# relay-set-d-decode.net
KiCad netlist of a schematic drawn in EAGLE
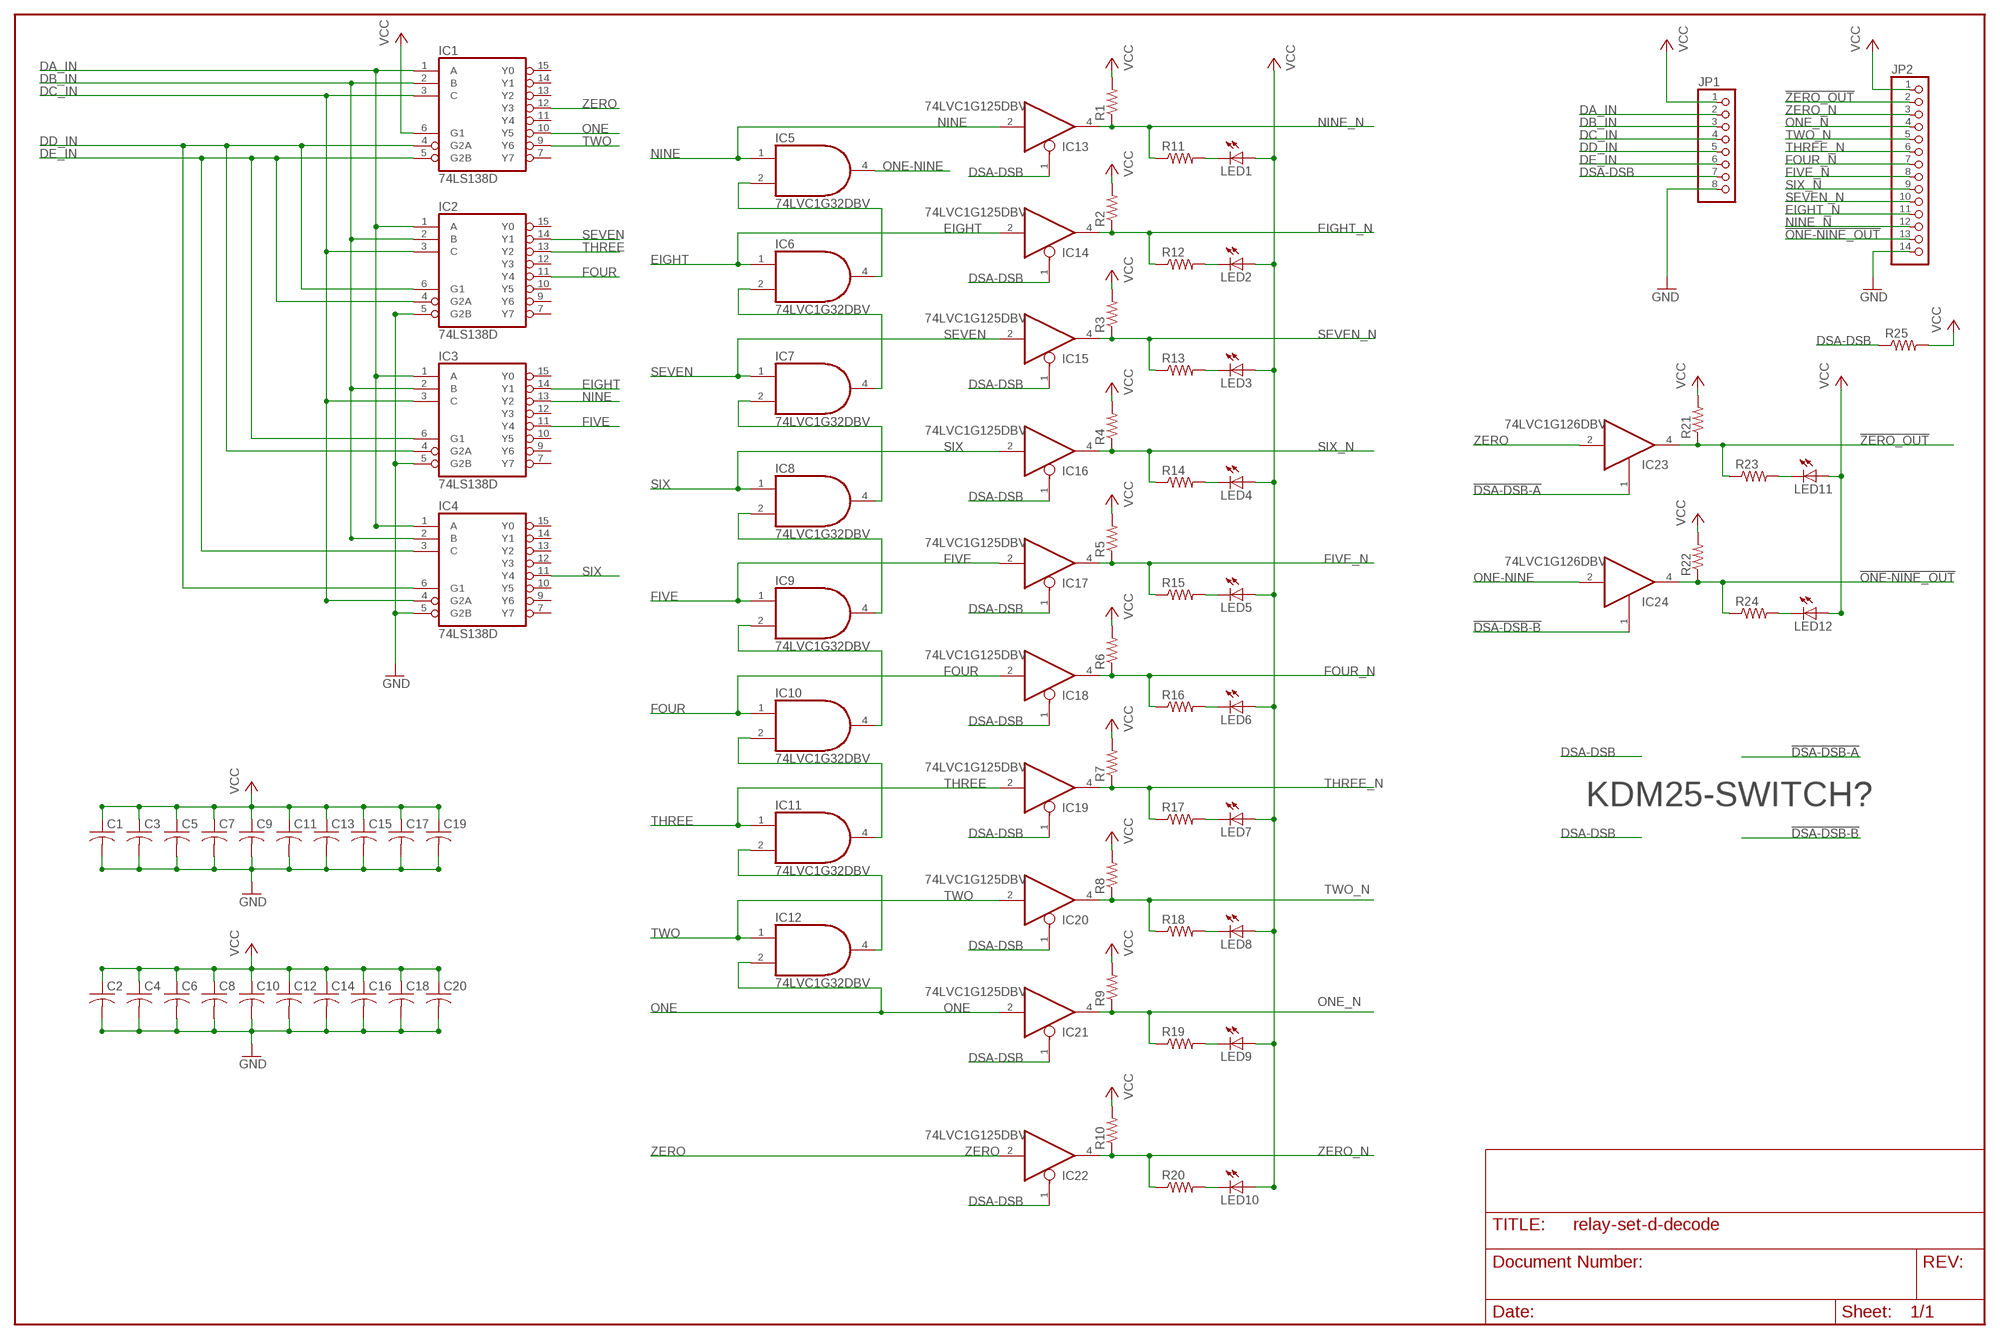
[diagram p0: schematic, sheet 1]

(export (version "E")
  (design (tool "Eeschema 10.0.6"))
  (components
    (comp (ref "C1")
      (value "C-USC0805")
      (footprint "eagle-import:C0805")
      (libsource (lib "eagle-import") (part "C-USC0805"))
    )
    (comp (ref "C2")
      (value "C-USC0805")
      (footprint "eagle-import:C0805")
      (libsource (lib "eagle-import") (part "C-USC0805"))
    )
    (comp (ref "C3")
      (value "C-USC0805")
      (footprint "eagle-import:C0805")
      (libsource (lib "eagle-import") (part "C-USC0805"))
    )
    (comp (ref "C4")
      (value "C-USC0805")
      (footprint "eagle-import:C0805")
      (libsource (lib "eagle-import") (part "C-USC0805"))
    )
    (comp (ref "C5")
      (value "C-USC0805")
      (footprint "eagle-import:C0805")
      (libsource (lib "eagle-import") (part "C-USC0805"))
    )
    (comp (ref "C6")
      (value "C-USC0805")
      (footprint "eagle-import:C0805")
      (libsource (lib "eagle-import") (part "C-USC0805"))
    )
    (comp (ref "C7")
      (value "C-USC0805")
      (footprint "eagle-import:C0805")
      (libsource (lib "eagle-import") (part "C-USC0805"))
    )
    (comp (ref "C8")
      (value "C-USC0805")
      (footprint "eagle-import:C0805")
      (libsource (lib "eagle-import") (part "C-USC0805"))
    )
    (comp (ref "C9")
      (value "C-USC0805")
      (footprint "eagle-import:C0805")
      (libsource (lib "eagle-import") (part "C-USC0805"))
    )
    (comp (ref "C10")
      (value "C-USC0805")
      (footprint "eagle-import:C0805")
      (libsource (lib "eagle-import") (part "C-USC0805"))
    )
    (comp (ref "C11")
      (value "C-USC0805")
      (footprint "eagle-import:C0805")
      (libsource (lib "eagle-import") (part "C-USC0805"))
    )
    (comp (ref "C12")
      (value "C-USC0805")
      (footprint "eagle-import:C0805")
      (libsource (lib "eagle-import") (part "C-USC0805"))
    )
    (comp (ref "C13")
      (value "C-USC0805")
      (footprint "eagle-import:C0805")
      (libsource (lib "eagle-import") (part "C-USC0805"))
    )
    (comp (ref "C14")
      (value "C-USC0805")
      (footprint "eagle-import:C0805")
      (libsource (lib "eagle-import") (part "C-USC0805"))
    )
    (comp (ref "C15")
      (value "C-USC0805")
      (footprint "eagle-import:C0805")
      (libsource (lib "eagle-import") (part "C-USC0805"))
    )
    (comp (ref "C16")
      (value "C-USC0805")
      (footprint "eagle-import:C0805")
      (libsource (lib "eagle-import") (part "C-USC0805"))
    )
    (comp (ref "C17")
      (value "C-USC0805")
      (footprint "eagle-import:C0805")
      (libsource (lib "eagle-import") (part "C-USC0805"))
    )
    (comp (ref "C18")
      (value "C-USC0805")
      (footprint "eagle-import:C0805")
      (libsource (lib "eagle-import") (part "C-USC0805"))
    )
    (comp (ref "C19")
      (value "C-USC0805")
      (footprint "eagle-import:C0805")
      (libsource (lib "eagle-import") (part "C-USC0805"))
    )
    (comp (ref "C20")
      (value "C-USC0805")
      (footprint "eagle-import:C0805")
      (libsource (lib "eagle-import") (part "C-USC0805"))
    )
    (comp (ref "IC1")
      (value "74LS138D")
      (footprint "eagle-import:SO16")
      (libsource (lib "eagle-import") (part "74138DLS"))
    )
    (comp (ref "IC2")
      (value "74LS138D")
      (footprint "eagle-import:SO16")
      (libsource (lib "eagle-import") (part "74138DLS"))
    )
    (comp (ref "IC3")
      (value "74LS138D")
      (footprint "eagle-import:SO16")
      (libsource (lib "eagle-import") (part "74138DLS"))
    )
    (comp (ref "IC4")
      (value "74LS138D")
      (footprint "eagle-import:SO16")
      (libsource (lib "eagle-import") (part "74138DLS"))
    )
    (comp (ref "IC5")
      (value "74LVC1G32DBV")
      (footprint "eagle-import:SOT23-5")
      (libsource (lib "eagle-import") (part "741G08DBVLVC"))
    )
    (comp (ref "IC6")
      (value "74LVC1G32DBV")
      (footprint "eagle-import:SOT23-5")
      (libsource (lib "eagle-import") (part "741G08DBVLVC"))
    )
    (comp (ref "IC7")
      (value "74LVC1G32DBV")
      (footprint "eagle-import:SOT23-5")
      (libsource (lib "eagle-import") (part "741G08DBVLVC"))
    )
    (comp (ref "IC8")
      (value "74LVC1G32DBV")
      (footprint "eagle-import:SOT23-5")
      (libsource (lib "eagle-import") (part "741G08DBVLVC"))
    )
    (comp (ref "IC9")
      (value "74LVC1G32DBV")
      (footprint "eagle-import:SOT23-5")
      (libsource (lib "eagle-import") (part "741G08DBVLVC"))
    )
    (comp (ref "IC10")
      (value "74LVC1G32DBV")
      (footprint "eagle-import:SOT23-5")
      (libsource (lib "eagle-import") (part "741G08DBVLVC"))
    )
    (comp (ref "IC11")
      (value "74LVC1G32DBV")
      (footprint "eagle-import:SOT23-5")
      (libsource (lib "eagle-import") (part "741G08DBVLVC"))
    )
    (comp (ref "IC12")
      (value "74LVC1G32DBV")
      (footprint "eagle-import:SOT23-5")
      (libsource (lib "eagle-import") (part "741G08DBVLVC"))
    )
    (comp (ref "IC13")
      (value "74LVC1G125DBV")
      (footprint "eagle-import:SOT23-5")
      (libsource (lib "eagle-import") (part "741G125DBVLVC"))
    )
    (comp (ref "IC14")
      (value "74LVC1G125DBV")
      (footprint "eagle-import:SOT23-5")
      (libsource (lib "eagle-import") (part "741G125DBVLVC"))
    )
    (comp (ref "IC15")
      (value "74LVC1G125DBV")
      (footprint "eagle-import:SOT23-5")
      (libsource (lib "eagle-import") (part "741G125DBVLVC"))
    )
    (comp (ref "IC16")
      (value "74LVC1G125DBV")
      (footprint "eagle-import:SOT23-5")
      (libsource (lib "eagle-import") (part "741G125DBVLVC"))
    )
    (comp (ref "IC17")
      (value "74LVC1G125DBV")
      (footprint "eagle-import:SOT23-5")
      (libsource (lib "eagle-import") (part "741G125DBVLVC"))
    )
    (comp (ref "IC18")
      (value "74LVC1G125DBV")
      (footprint "eagle-import:SOT23-5")
      (libsource (lib "eagle-import") (part "741G125DBVLVC"))
    )
    (comp (ref "IC19")
      (value "74LVC1G125DBV")
      (footprint "eagle-import:SOT23-5")
      (libsource (lib "eagle-import") (part "741G125DBVLVC"))
    )
    (comp (ref "IC20")
      (value "74LVC1G125DBV")
      (footprint "eagle-import:SOT23-5")
      (libsource (lib "eagle-import") (part "741G125DBVLVC"))
    )
    (comp (ref "IC21")
      (value "74LVC1G125DBV")
      (footprint "eagle-import:SOT23-5")
      (libsource (lib "eagle-import") (part "741G125DBVLVC"))
    )
    (comp (ref "IC22")
      (value "74LVC1G125DBV")
      (footprint "eagle-import:SOT23-5")
      (libsource (lib "eagle-import") (part "741G125DBVLVC"))
    )
    (comp (ref "IC23")
      (value "74LVC1G126DBV")
      (footprint "eagle-import:SOT23-5")
      (libsource (lib "eagle-import") (part "741G126DBVLVC"))
    )
    (comp (ref "IC24")
      (value "74LVC1G126DBV")
      (footprint "eagle-import:SOT23-5")
      (libsource (lib "eagle-import") (part "741G126DBVLVC"))
    )
    (comp (ref "JP1")
      (value "PINHD-1X8")
      (footprint "eagle-import:1X08")
      (libsource (lib "eagle-import") (part "PINHD-1X8"))
    )
    (comp (ref "JP2")
      (value "PINHD-1X14")
      (footprint "eagle-import:1X14")
      (libsource (lib "eagle-import") (part "PINHD-1X14"))
    )
    (comp (ref "LED1")
      (value "LEDCHIP-LED0805")
      (footprint "eagle-import:CHIP-LED0805")
      (libsource (lib "eagle-import") (part "LEDCHIP-LED0805"))
    )
    (comp (ref "LED2")
      (value "LEDCHIP-LED0805")
      (footprint "eagle-import:CHIP-LED0805")
      (libsource (lib "eagle-import") (part "LEDCHIP-LED0805"))
    )
    (comp (ref "LED3")
      (value "LEDCHIP-LED0805")
      (footprint "eagle-import:CHIP-LED0805")
      (libsource (lib "eagle-import") (part "LEDCHIP-LED0805"))
    )
    (comp (ref "LED4")
      (value "LEDCHIP-LED0805")
      (footprint "eagle-import:CHIP-LED0805")
      (libsource (lib "eagle-import") (part "LEDCHIP-LED0805"))
    )
    (comp (ref "LED5")
      (value "LEDCHIP-LED0805")
      (footprint "eagle-import:CHIP-LED0805")
      (libsource (lib "eagle-import") (part "LEDCHIP-LED0805"))
    )
    (comp (ref "LED6")
      (value "LEDCHIP-LED0805")
      (footprint "eagle-import:CHIP-LED0805")
      (libsource (lib "eagle-import") (part "LEDCHIP-LED0805"))
    )
    (comp (ref "LED7")
      (value "LEDCHIP-LED0805")
      (footprint "eagle-import:CHIP-LED0805")
      (libsource (lib "eagle-import") (part "LEDCHIP-LED0805"))
    )
    (comp (ref "LED8")
      (value "LEDCHIP-LED0805")
      (footprint "eagle-import:CHIP-LED0805")
      (libsource (lib "eagle-import") (part "LEDCHIP-LED0805"))
    )
    (comp (ref "LED9")
      (value "LEDCHIP-LED0805")
      (footprint "eagle-import:CHIP-LED0805")
      (libsource (lib "eagle-import") (part "LEDCHIP-LED0805"))
    )
    (comp (ref "LED10")
      (value "LEDCHIP-LED0805")
      (footprint "eagle-import:CHIP-LED0805")
      (libsource (lib "eagle-import") (part "LEDCHIP-LED0805"))
    )
    (comp (ref "LED11")
      (value "LEDCHIP-LED0805")
      (footprint "eagle-import:CHIP-LED0805")
      (libsource (lib "eagle-import") (part "LEDCHIP-LED0805"))
    )
    (comp (ref "LED12")
      (value "LEDCHIP-LED0805")
      (footprint "eagle-import:CHIP-LED0805")
      (libsource (lib "eagle-import") (part "LEDCHIP-LED0805"))
    )
    (comp (ref "R1")
      (value "R-US_R0805")
      (footprint "eagle-import:R0805")
      (libsource (lib "eagle-import") (part "R-US_R0805"))
    )
    (comp (ref "R2")
      (value "R-US_R0805")
      (footprint "eagle-import:R0805")
      (libsource (lib "eagle-import") (part "R-US_R0805"))
    )
    (comp (ref "R3")
      (value "R-US_R0805")
      (footprint "eagle-import:R0805")
      (libsource (lib "eagle-import") (part "R-US_R0805"))
    )
    (comp (ref "R4")
      (value "R-US_R0805")
      (footprint "eagle-import:R0805")
      (libsource (lib "eagle-import") (part "R-US_R0805"))
    )
    (comp (ref "R5")
      (value "R-US_R0805")
      (footprint "eagle-import:R0805")
      (libsource (lib "eagle-import") (part "R-US_R0805"))
    )
    (comp (ref "R6")
      (value "R-US_R0805")
      (footprint "eagle-import:R0805")
      (libsource (lib "eagle-import") (part "R-US_R0805"))
    )
    (comp (ref "R7")
      (value "R-US_R0805")
      (footprint "eagle-import:R0805")
      (libsource (lib "eagle-import") (part "R-US_R0805"))
    )
    (comp (ref "R8")
      (value "R-US_R0805")
      (footprint "eagle-import:R0805")
      (libsource (lib "eagle-import") (part "R-US_R0805"))
    )
    (comp (ref "R9")
      (value "R-US_R0805")
      (footprint "eagle-import:R0805")
      (libsource (lib "eagle-import") (part "R-US_R0805"))
    )
    (comp (ref "R10")
      (value "R-US_R0805")
      (footprint "eagle-import:R0805")
      (libsource (lib "eagle-import") (part "R-US_R0805"))
    )
    (comp (ref "R11")
      (value "R-US_R0805")
      (footprint "eagle-import:R0805")
      (libsource (lib "eagle-import") (part "R-US_R0805"))
    )
    (comp (ref "R12")
      (value "R-US_R0805")
      (footprint "eagle-import:R0805")
      (libsource (lib "eagle-import") (part "R-US_R0805"))
    )
    (comp (ref "R13")
      (value "R-US_R0805")
      (footprint "eagle-import:R0805")
      (libsource (lib "eagle-import") (part "R-US_R0805"))
    )
    (comp (ref "R14")
      (value "R-US_R0805")
      (footprint "eagle-import:R0805")
      (libsource (lib "eagle-import") (part "R-US_R0805"))
    )
    (comp (ref "R15")
      (value "R-US_R0805")
      (footprint "eagle-import:R0805")
      (libsource (lib "eagle-import") (part "R-US_R0805"))
    )
    (comp (ref "R16")
      (value "R-US_R0805")
      (footprint "eagle-import:R0805")
      (libsource (lib "eagle-import") (part "R-US_R0805"))
    )
    (comp (ref "R17")
      (value "R-US_R0805")
      (footprint "eagle-import:R0805")
      (libsource (lib "eagle-import") (part "R-US_R0805"))
    )
    (comp (ref "R18")
      (value "R-US_R0805")
      (footprint "eagle-import:R0805")
      (libsource (lib "eagle-import") (part "R-US_R0805"))
    )
    (comp (ref "R19")
      (value "R-US_R0805")
      (footprint "eagle-import:R0805")
      (libsource (lib "eagle-import") (part "R-US_R0805"))
    )
    (comp (ref "R20")
      (value "R-US_R0805")
      (footprint "eagle-import:R0805")
      (libsource (lib "eagle-import") (part "R-US_R0805"))
    )
    (comp (ref "R21")
      (value "R-US_R0805")
      (footprint "eagle-import:R0805")
      (libsource (lib "eagle-import") (part "R-US_R0805"))
    )
    (comp (ref "R22")
      (value "R-US_R0805")
      (footprint "eagle-import:R0805")
      (libsource (lib "eagle-import") (part "R-US_R0805"))
    )
    (comp (ref "R23")
      (value "R-US_R0805")
      (footprint "eagle-import:R0805")
      (libsource (lib "eagle-import") (part "R-US_R0805"))
    )
    (comp (ref "R24")
      (value "R-US_R0805")
      (footprint "eagle-import:R0805")
      (libsource (lib "eagle-import") (part "R-US_R0805"))
    )
    (comp (ref "R25")
      (value "R-US_R0805")
      (footprint "eagle-import:R0805")
      (libsource (lib "eagle-import") (part "R-US_R0805"))
    )
  )
  (nets
    (net (code "1") (name "/DA_IN") (class "Default")
      (node (ref "IC1") (pin "1") (pinfunction "A_1") (pintype "input"))
      (node (ref "IC2") (pin "1") (pinfunction "A_1") (pintype "input"))
      (node (ref "IC3") (pin "1") (pinfunction "A_1") (pintype "input"))
      (node (ref "IC4") (pin "1") (pinfunction "A_1") (pintype "input"))
      (node (ref "JP1") (pin "2") (pinfunction "2_2") (pintype "passive"))
    )
    (net (code "2") (name "/DB_IN") (class "Default")
      (node (ref "IC1") (pin "2") (pinfunction "B_2") (pintype "input"))
      (node (ref "IC2") (pin "2") (pinfunction "B_2") (pintype "input"))
      (node (ref "IC3") (pin "2") (pinfunction "B_2") (pintype "input"))
      (node (ref "IC4") (pin "2") (pinfunction "B_2") (pintype "input"))
      (node (ref "JP1") (pin "3") (pinfunction "3_3") (pintype "passive"))
    )
    (net (code "3") (name "/DC_IN") (class "Default")
      (node (ref "IC1") (pin "3") (pinfunction "C_3") (pintype "input"))
      (node (ref "IC2") (pin "3") (pinfunction "C_3") (pintype "input"))
      (node (ref "IC3") (pin "3") (pinfunction "C_3") (pintype "input"))
      (node (ref "IC4") (pin "4") (pinfunction "G2A_4") (pintype "input"))
      (node (ref "JP1") (pin "4") (pinfunction "4_4") (pintype "passive"))
    )
    (net (code "4") (name "/DD_IN") (class "Default")
      (node (ref "IC1") (pin "4") (pinfunction "G2A_4") (pintype "input"))
      (node (ref "IC2") (pin "6") (pinfunction "G1_6") (pintype "input"))
      (node (ref "IC3") (pin "4") (pinfunction "G2A_4") (pintype "input"))
      (node (ref "IC4") (pin "6") (pinfunction "G1_6") (pintype "input"))
      (node (ref "JP1") (pin "5") (pinfunction "5_5") (pintype "passive"))
    )
    (net (code "5") (name "/DE_IN") (class "Default")
      (node (ref "IC1") (pin "5") (pinfunction "G2B_5") (pintype "input"))
      (node (ref "IC2") (pin "4") (pinfunction "G2A_4") (pintype "input"))
      (node (ref "IC3") (pin "6") (pinfunction "G1_6") (pintype "input"))
      (node (ref "IC4") (pin "3") (pinfunction "C_3") (pintype "input"))
      (node (ref "JP1") (pin "6") (pinfunction "6_6") (pintype "passive"))
    )
    (net (code "6") (name "/DSA-DSB") (class "Default")
      (node (ref "IC13") (pin "1") (pinfunction "OE_1") (pintype "input"))
      (node (ref "IC14") (pin "1") (pinfunction "OE_1") (pintype "input"))
      (node (ref "IC15") (pin "1") (pinfunction "OE_1") (pintype "input"))
      (node (ref "IC16") (pin "1") (pinfunction "OE_1") (pintype "input"))
      (node (ref "IC17") (pin "1") (pinfunction "OE_1") (pintype "input"))
      (node (ref "IC18") (pin "1") (pinfunction "OE_1") (pintype "input"))
      (node (ref "IC19") (pin "1") (pinfunction "OE_1") (pintype "input"))
      (node (ref "IC20") (pin "1") (pinfunction "OE_1") (pintype "input"))
      (node (ref "IC21") (pin "1") (pinfunction "OE_1") (pintype "input"))
      (node (ref "IC22") (pin "1") (pinfunction "OE_1") (pintype "input"))
      (node (ref "JP1") (pin "7") (pinfunction "7_7") (pintype "passive"))
      (node (ref "R25") (pin "1") (pinfunction "1_1") (pintype "passive"))
    )
    (net (code "7") (name "/EIGHT") (class "Default")
      (node (ref "IC14") (pin "2") (pinfunction "I_2") (pintype "input"))
      (node (ref "IC3") (pin "14") (pinfunction "Y1_14") (pintype "output"))
      (node (ref "IC6") (pin "1") (pinfunction "I0_1") (pintype "input"))
    )
    (net (code "8") (name "/EIGHT_N") (class "Default")
      (node (ref "IC14") (pin "4") (pinfunction "O_4") (pintype "tri_state"))
      (node (ref "JP2") (pin "11") (pinfunction "11_11") (pintype "passive"))
      (node (ref "R12") (pin "1") (pinfunction "1_1") (pintype "passive"))
      (node (ref "R2") (pin "1") (pinfunction "1_1") (pintype "passive"))
    )
    (net (code "9") (name "/FIVE") (class "Default")
      (node (ref "IC17") (pin "2") (pinfunction "I_2") (pintype "input"))
      (node (ref "IC3") (pin "11") (pinfunction "Y4_11") (pintype "output"))
      (node (ref "IC9") (pin "1") (pinfunction "I0_1") (pintype "input"))
    )
    (net (code "10") (name "/FIVE_N") (class "Default")
      (node (ref "IC17") (pin "4") (pinfunction "O_4") (pintype "tri_state"))
      (node (ref "JP2") (pin "8") (pinfunction "8_8") (pintype "passive"))
      (node (ref "R15") (pin "1") (pinfunction "1_1") (pintype "passive"))
      (node (ref "R5") (pin "1") (pinfunction "1_1") (pintype "passive"))
    )
    (net (code "11") (name "/FOUR") (class "Default")
      (node (ref "IC10") (pin "1") (pinfunction "I0_1") (pintype "input"))
      (node (ref "IC18") (pin "2") (pinfunction "I_2") (pintype "input"))
      (node (ref "IC2") (pin "11") (pinfunction "Y4_11") (pintype "output"))
    )
    (net (code "12") (name "/FOUR_N") (class "Default")
      (node (ref "IC18") (pin "4") (pinfunction "O_4") (pintype "tri_state"))
      (node (ref "JP2") (pin "7") (pinfunction "7_7") (pintype "passive"))
      (node (ref "R16") (pin "1") (pinfunction "1_1") (pintype "passive"))
      (node (ref "R6") (pin "1") (pinfunction "1_1") (pintype "passive"))
    )
    (net (code "13") (name "/NINE") (class "Default")
      (node (ref "IC13") (pin "2") (pinfunction "I_2") (pintype "input"))
      (node (ref "IC3") (pin "13") (pinfunction "Y2_13") (pintype "output"))
      (node (ref "IC5") (pin "1") (pinfunction "I0_1") (pintype "input"))
    )
    (net (code "14") (name "/NINE_N") (class "Default")
      (node (ref "IC13") (pin "4") (pinfunction "O_4") (pintype "tri_state"))
      (node (ref "JP2") (pin "12") (pinfunction "12_12") (pintype "passive"))
      (node (ref "R1") (pin "1") (pinfunction "1_1") (pintype "passive"))
      (node (ref "R11") (pin "1") (pinfunction "1_1") (pintype "passive"))
    )
    (net (code "15") (name "/ONE") (class "Default")
      (node (ref "IC1") (pin "10") (pinfunction "Y5_10") (pintype "output"))
      (node (ref "IC12") (pin "2") (pinfunction "I1_2") (pintype "input"))
      (node (ref "IC21") (pin "2") (pinfunction "I_2") (pintype "input"))
    )
    (net (code "16") (name "/ONE-NINE") (class "Default")
      (node (ref "IC24") (pin "2") (pinfunction "I_2") (pintype "input"))
      (node (ref "IC5") (pin "4") (pinfunction "O_4") (pintype "output"))
    )
    (net (code "17") (name "/ONE_N") (class "Default")
      (node (ref "IC21") (pin "4") (pinfunction "O_4") (pintype "tri_state"))
      (node (ref "JP2") (pin "4") (pinfunction "4_4") (pintype "passive"))
      (node (ref "R19") (pin "1") (pinfunction "1_1") (pintype "passive"))
      (node (ref "R9") (pin "1") (pinfunction "1_1") (pintype "passive"))
    )
    (net (code "18") (name "/SEVEN") (class "Default")
      (node (ref "IC15") (pin "2") (pinfunction "I_2") (pintype "input"))
      (node (ref "IC2") (pin "14") (pinfunction "Y1_14") (pintype "output"))
      (node (ref "IC7") (pin "1") (pinfunction "I0_1") (pintype "input"))
    )
    (net (code "19") (name "/SEVEN_N") (class "Default")
      (node (ref "IC15") (pin "4") (pinfunction "O_4") (pintype "tri_state"))
      (node (ref "JP2") (pin "10") (pinfunction "10_10") (pintype "passive"))
      (node (ref "R13") (pin "1") (pinfunction "1_1") (pintype "passive"))
      (node (ref "R3") (pin "1") (pinfunction "1_1") (pintype "passive"))
    )
    (net (code "20") (name "/SIX") (class "Default")
      (node (ref "IC16") (pin "2") (pinfunction "I_2") (pintype "input"))
      (node (ref "IC4") (pin "11") (pinfunction "Y4_11") (pintype "output"))
      (node (ref "IC8") (pin "1") (pinfunction "I0_1") (pintype "input"))
    )
    (net (code "21") (name "/SIX_N") (class "Default")
      (node (ref "IC16") (pin "4") (pinfunction "O_4") (pintype "tri_state"))
      (node (ref "JP2") (pin "9") (pinfunction "9_9") (pintype "passive"))
      (node (ref "R14") (pin "1") (pinfunction "1_1") (pintype "passive"))
      (node (ref "R4") (pin "1") (pinfunction "1_1") (pintype "passive"))
    )
    (net (code "22") (name "/THREE") (class "Default")
      (node (ref "IC11") (pin "1") (pinfunction "I0_1") (pintype "input"))
      (node (ref "IC19") (pin "2") (pinfunction "I_2") (pintype "input"))
      (node (ref "IC2") (pin "13") (pinfunction "Y2_13") (pintype "output"))
    )
    (net (code "23") (name "/THREE_N") (class "Default")
      (node (ref "IC19") (pin "4") (pinfunction "O_4") (pintype "tri_state"))
      (node (ref "JP2") (pin "6") (pinfunction "6_6") (pintype "passive"))
      (node (ref "R17") (pin "1") (pinfunction "1_1") (pintype "passive"))
      (node (ref "R7") (pin "1") (pinfunction "1_1") (pintype "passive"))
    )
    (net (code "24") (name "/TWO") (class "Default")
      (node (ref "IC1") (pin "9") (pinfunction "Y6_9") (pintype "output"))
      (node (ref "IC12") (pin "1") (pinfunction "I0_1") (pintype "input"))
      (node (ref "IC20") (pin "2") (pinfunction "I_2") (pintype "input"))
    )
    (net (code "25") (name "/TWO_N") (class "Default")
      (node (ref "IC20") (pin "4") (pinfunction "O_4") (pintype "tri_state"))
      (node (ref "JP2") (pin "5") (pinfunction "5_5") (pintype "passive"))
      (node (ref "R18") (pin "1") (pinfunction "1_1") (pintype "passive"))
      (node (ref "R8") (pin "1") (pinfunction "1_1") (pintype "passive"))
    )
    (net (code "26") (name "/ZERO") (class "Default")
      (node (ref "IC1") (pin "12") (pinfunction "Y3_12") (pintype "output"))
      (node (ref "IC22") (pin "2") (pinfunction "I_2") (pintype "input"))
      (node (ref "IC23") (pin "2") (pinfunction "I_2") (pintype "input"))
    )
    (net (code "27") (name "/ZERO_N") (class "Default")
      (node (ref "IC22") (pin "4") (pinfunction "O_4") (pintype "tri_state"))
      (node (ref "JP2") (pin "3") (pinfunction "3_3") (pintype "passive"))
      (node (ref "R10") (pin "1") (pinfunction "1_1") (pintype "passive"))
      (node (ref "R20") (pin "1") (pinfunction "1_1") (pintype "passive"))
    )
    (net (code "28") (name "/~{DSA-DSB-A}") (class "Default")
      (node (ref "IC23") (pin "1") (pinfunction "OE_1") (pintype "input"))
    )
    (net (code "29") (name "/~{DSA-DSB-B}") (class "Default")
      (node (ref "IC24") (pin "1") (pinfunction "OE_1") (pintype "input"))
    )
    (net (code "30") (name "/~{ONE-NINE_OUT}") (class "Default")
      (node (ref "IC24") (pin "4") (pinfunction "O_4") (pintype "output"))
      (node (ref "JP2") (pin "13") (pinfunction "13_13") (pintype "passive"))
      (node (ref "R22") (pin "1") (pinfunction "1_1") (pintype "passive"))
      (node (ref "R24") (pin "1") (pinfunction "1_1") (pintype "passive"))
    )
    (net (code "31") (name "/~{ZERO_OUT}") (class "Default")
      (node (ref "IC23") (pin "4") (pinfunction "O_4") (pintype "output"))
      (node (ref "JP2") (pin "2") (pinfunction "2_2") (pintype "passive"))
      (node (ref "R21") (pin "1") (pinfunction "1_1") (pintype "passive"))
      (node (ref "R23") (pin "1") (pinfunction "1_1") (pintype "passive"))
    )
    (net (code "32") (name "GND") (class "Default")
      (node (ref "C1") (pin "2") (pinfunction "2_2") (pintype "passive"))
      (node (ref "C10") (pin "2") (pinfunction "2_2") (pintype "passive"))
      (node (ref "C11") (pin "2") (pinfunction "2_2") (pintype "passive"))
      (node (ref "C12") (pin "2") (pinfunction "2_2") (pintype "passive"))
      (node (ref "C13") (pin "2") (pinfunction "2_2") (pintype "passive"))
      (node (ref "C14") (pin "2") (pinfunction "2_2") (pintype "passive"))
      (node (ref "C15") (pin "2") (pinfunction "2_2") (pintype "passive"))
      (node (ref "C16") (pin "2") (pinfunction "2_2") (pintype "passive"))
      (node (ref "C17") (pin "2") (pinfunction "2_2") (pintype "passive"))
      (node (ref "C18") (pin "2") (pinfunction "2_2") (pintype "passive"))
      (node (ref "C19") (pin "2") (pinfunction "2_2") (pintype "passive"))
      (node (ref "C2") (pin "2") (pinfunction "2_2") (pintype "passive"))
      (node (ref "C20") (pin "2") (pinfunction "2_2") (pintype "passive"))
      (node (ref "C3") (pin "2") (pinfunction "2_2") (pintype "passive"))
      (node (ref "C4") (pin "2") (pinfunction "2_2") (pintype "passive"))
      (node (ref "C5") (pin "2") (pinfunction "2_2") (pintype "passive"))
      (node (ref "C6") (pin "2") (pinfunction "2_2") (pintype "passive"))
      (node (ref "C7") (pin "2") (pinfunction "2_2") (pintype "passive"))
      (node (ref "C8") (pin "2") (pinfunction "2_2") (pintype "passive"))
      (node (ref "C9") (pin "2") (pinfunction "2_2") (pintype "passive"))
      (node (ref "IC2") (pin "5") (pinfunction "G2B_5") (pintype "input"))
      (node (ref "IC3") (pin "5") (pinfunction "G2B_5") (pintype "input"))
      (node (ref "IC4") (pin "5") (pinfunction "G2B_5") (pintype "input"))
      (node (ref "JP1") (pin "8") (pinfunction "8_8") (pintype "passive"))
      (node (ref "JP2") (pin "14") (pinfunction "14_14") (pintype "passive"))
    )
    (net (code "33") (name "Net-(IC5A-I1)") (class "Default")
      (node (ref "IC5") (pin "2") (pinfunction "I1_2") (pintype "input"))
      (node (ref "IC6") (pin "4") (pinfunction "O_4") (pintype "output"))
    )
    (net (code "34") (name "Net-(IC6A-I1)") (class "Default")
      (node (ref "IC6") (pin "2") (pinfunction "I1_2") (pintype "input"))
      (node (ref "IC7") (pin "4") (pinfunction "O_4") (pintype "output"))
    )
    (net (code "35") (name "Net-(IC7A-I1)") (class "Default")
      (node (ref "IC7") (pin "2") (pinfunction "I1_2") (pintype "input"))
      (node (ref "IC8") (pin "4") (pinfunction "O_4") (pintype "output"))
    )
    (net (code "36") (name "Net-(IC8A-I1)") (class "Default")
      (node (ref "IC8") (pin "2") (pinfunction "I1_2") (pintype "input"))
      (node (ref "IC9") (pin "4") (pinfunction "O_4") (pintype "output"))
    )
    (net (code "37") (name "Net-(IC10A-I1)") (class "Default")
      (node (ref "IC10") (pin "2") (pinfunction "I1_2") (pintype "input"))
      (node (ref "IC11") (pin "4") (pinfunction "O_4") (pintype "output"))
    )
    (net (code "38") (name "Net-(IC10A-O)") (class "Default")
      (node (ref "IC10") (pin "4") (pinfunction "O_4") (pintype "output"))
      (node (ref "IC9") (pin "2") (pinfunction "I1_2") (pintype "input"))
    )
    (net (code "39") (name "Net-(IC11A-I1)") (class "Default")
      (node (ref "IC11") (pin "2") (pinfunction "I1_2") (pintype "input"))
      (node (ref "IC12") (pin "4") (pinfunction "O_4") (pintype "output"))
    )
    (net (code "40") (name "Net-(LED1-PadC)") (class "Default")
      (node (ref "LED1") (pin "C") (pinfunction "C_C") (pintype "passive"))
      (node (ref "R11") (pin "2") (pinfunction "2_2") (pintype "passive"))
    )
    (net (code "41") (name "Net-(LED2-PadC)") (class "Default")
      (node (ref "LED2") (pin "C") (pinfunction "C_C") (pintype "passive"))
      (node (ref "R12") (pin "2") (pinfunction "2_2") (pintype "passive"))
    )
    (net (code "42") (name "Net-(LED3-PadC)") (class "Default")
      (node (ref "LED3") (pin "C") (pinfunction "C_C") (pintype "passive"))
      (node (ref "R13") (pin "2") (pinfunction "2_2") (pintype "passive"))
    )
    (net (code "43") (name "Net-(LED4-PadC)") (class "Default")
      (node (ref "LED4") (pin "C") (pinfunction "C_C") (pintype "passive"))
      (node (ref "R14") (pin "2") (pinfunction "2_2") (pintype "passive"))
    )
    (net (code "44") (name "Net-(LED5-PadC)") (class "Default")
      (node (ref "LED5") (pin "C") (pinfunction "C_C") (pintype "passive"))
      (node (ref "R15") (pin "2") (pinfunction "2_2") (pintype "passive"))
    )
    (net (code "45") (name "Net-(LED6-PadC)") (class "Default")
      (node (ref "LED6") (pin "C") (pinfunction "C_C") (pintype "passive"))
      (node (ref "R16") (pin "2") (pinfunction "2_2") (pintype "passive"))
    )
    (net (code "46") (name "Net-(LED7-PadC)") (class "Default")
      (node (ref "LED7") (pin "C") (pinfunction "C_C") (pintype "passive"))
      (node (ref "R17") (pin "2") (pinfunction "2_2") (pintype "passive"))
    )
    (net (code "47") (name "Net-(LED8-PadC)") (class "Default")
      (node (ref "LED8") (pin "C") (pinfunction "C_C") (pintype "passive"))
      (node (ref "R18") (pin "2") (pinfunction "2_2") (pintype "passive"))
    )
    (net (code "48") (name "Net-(LED9-PadC)") (class "Default")
      (node (ref "LED9") (pin "C") (pinfunction "C_C") (pintype "passive"))
      (node (ref "R19") (pin "2") (pinfunction "2_2") (pintype "passive"))
    )
    (net (code "49") (name "Net-(LED10-PadC)") (class "Default")
      (node (ref "LED10") (pin "C") (pinfunction "C_C") (pintype "passive"))
      (node (ref "R20") (pin "2") (pinfunction "2_2") (pintype "passive"))
    )
    (net (code "50") (name "Net-(LED11-PadC)") (class "Default")
      (node (ref "LED11") (pin "C") (pinfunction "C_C") (pintype "passive"))
      (node (ref "R23") (pin "2") (pinfunction "2_2") (pintype "passive"))
    )
    (net (code "51") (name "Net-(LED12-PadC)") (class "Default")
      (node (ref "LED12") (pin "C") (pinfunction "C_C") (pintype "passive"))
      (node (ref "R24") (pin "2") (pinfunction "2_2") (pintype "passive"))
    )
    (net (code "52") (name "VCC") (class "Default")
      (node (ref "C1") (pin "1") (pinfunction "1_1") (pintype "passive"))
      (node (ref "C10") (pin "1") (pinfunction "1_1") (pintype "passive"))
      (node (ref "C11") (pin "1") (pinfunction "1_1") (pintype "passive"))
      (node (ref "C12") (pin "1") (pinfunction "1_1") (pintype "passive"))
      (node (ref "C13") (pin "1") (pinfunction "1_1") (pintype "passive"))
      (node (ref "C14") (pin "1") (pinfunction "1_1") (pintype "passive"))
      (node (ref "C15") (pin "1") (pinfunction "1_1") (pintype "passive"))
      (node (ref "C16") (pin "1") (pinfunction "1_1") (pintype "passive"))
      (node (ref "C17") (pin "1") (pinfunction "1_1") (pintype "passive"))
      (node (ref "C18") (pin "1") (pinfunction "1_1") (pintype "passive"))
      (node (ref "C19") (pin "1") (pinfunction "1_1") (pintype "passive"))
      (node (ref "C2") (pin "1") (pinfunction "1_1") (pintype "passive"))
      (node (ref "C20") (pin "1") (pinfunction "1_1") (pintype "passive"))
      (node (ref "C3") (pin "1") (pinfunction "1_1") (pintype "passive"))
      (node (ref "C4") (pin "1") (pinfunction "1_1") (pintype "passive"))
      (node (ref "C5") (pin "1") (pinfunction "1_1") (pintype "passive"))
      (node (ref "C6") (pin "1") (pinfunction "1_1") (pintype "passive"))
      (node (ref "C7") (pin "1") (pinfunction "1_1") (pintype "passive"))
      (node (ref "C8") (pin "1") (pinfunction "1_1") (pintype "passive"))
      (node (ref "C9") (pin "1") (pinfunction "1_1") (pintype "passive"))
      (node (ref "IC1") (pin "6") (pinfunction "G1_6") (pintype "input"))
      (node (ref "JP1") (pin "1") (pinfunction "1_1") (pintype "passive"))
      (node (ref "JP2") (pin "1") (pinfunction "1_1") (pintype "passive"))
      (node (ref "LED1") (pin "A") (pinfunction "A_A") (pintype "passive"))
      (node (ref "LED10") (pin "A") (pinfunction "A_A") (pintype "passive"))
      (node (ref "LED11") (pin "A") (pinfunction "A_A") (pintype "passive"))
      (node (ref "LED12") (pin "A") (pinfunction "A_A") (pintype "passive"))
      (node (ref "LED2") (pin "A") (pinfunction "A_A") (pintype "passive"))
      (node (ref "LED3") (pin "A") (pinfunction "A_A") (pintype "passive"))
      (node (ref "LED4") (pin "A") (pinfunction "A_A") (pintype "passive"))
      (node (ref "LED5") (pin "A") (pinfunction "A_A") (pintype "passive"))
      (node (ref "LED6") (pin "A") (pinfunction "A_A") (pintype "passive"))
      (node (ref "LED7") (pin "A") (pinfunction "A_A") (pintype "passive"))
      (node (ref "LED8") (pin "A") (pinfunction "A_A") (pintype "passive"))
      (node (ref "LED9") (pin "A") (pinfunction "A_A") (pintype "passive"))
      (node (ref "R1") (pin "2") (pinfunction "2_2") (pintype "passive"))
      (node (ref "R10") (pin "2") (pinfunction "2_2") (pintype "passive"))
      (node (ref "R2") (pin "2") (pinfunction "2_2") (pintype "passive"))
      (node (ref "R21") (pin "2") (pinfunction "2_2") (pintype "passive"))
      (node (ref "R22") (pin "2") (pinfunction "2_2") (pintype "passive"))
      (node (ref "R25") (pin "2") (pinfunction "2_2") (pintype "passive"))
      (node (ref "R3") (pin "2") (pinfunction "2_2") (pintype "passive"))
      (node (ref "R4") (pin "2") (pinfunction "2_2") (pintype "passive"))
      (node (ref "R5") (pin "2") (pinfunction "2_2") (pintype "passive"))
      (node (ref "R6") (pin "2") (pinfunction "2_2") (pintype "passive"))
      (node (ref "R7") (pin "2") (pinfunction "2_2") (pintype "passive"))
      (node (ref "R8") (pin "2") (pinfunction "2_2") (pintype "passive"))
      (node (ref "R9") (pin "2") (pinfunction "2_2") (pintype "passive"))
    )
    (net (code "53") (name "unconnected-(IC1A-Y0-Pad15)") (class "Default")
      (node (ref "IC1") (pin "15") (pinfunction "Y0_15") (pintype "output"))
    )
    (net (code "54") (name "unconnected-(IC1A-Y1-Pad14)") (class "Default")
      (node (ref "IC1") (pin "14") (pinfunction "Y1_14") (pintype "output"))
    )
    (net (code "55") (name "unconnected-(IC1A-Y2-Pad13)") (class "Default")
      (node (ref "IC1") (pin "13") (pinfunction "Y2_13") (pintype "output"))
    )
    (net (code "56") (name "unconnected-(IC1A-Y4-Pad11)") (class "Default")
      (node (ref "IC1") (pin "11") (pinfunction "Y4_11") (pintype "output"))
    )
    (net (code "57") (name "unconnected-(IC1A-Y7-Pad7)") (class "Default")
      (node (ref "IC1") (pin "7") (pinfunction "Y7_7") (pintype "output"))
    )
    (net (code "58") (name "unconnected-(IC2A-Y0-Pad15)") (class "Default")
      (node (ref "IC2") (pin "15") (pinfunction "Y0_15") (pintype "output"))
    )
    (net (code "59") (name "unconnected-(IC2A-Y3-Pad12)") (class "Default")
      (node (ref "IC2") (pin "12") (pinfunction "Y3_12") (pintype "output"))
    )
    (net (code "60") (name "unconnected-(IC2A-Y5-Pad10)") (class "Default")
      (node (ref "IC2") (pin "10") (pinfunction "Y5_10") (pintype "output"))
    )
    (net (code "61") (name "unconnected-(IC2A-Y6-Pad9)") (class "Default")
      (node (ref "IC2") (pin "9") (pinfunction "Y6_9") (pintype "output"))
    )
    (net (code "62") (name "unconnected-(IC2A-Y7-Pad7)") (class "Default")
      (node (ref "IC2") (pin "7") (pinfunction "Y7_7") (pintype "output"))
    )
    (net (code "63") (name "unconnected-(IC3A-Y0-Pad15)") (class "Default")
      (node (ref "IC3") (pin "15") (pinfunction "Y0_15") (pintype "output"))
    )
    (net (code "64") (name "unconnected-(IC3A-Y3-Pad12)") (class "Default")
      (node (ref "IC3") (pin "12") (pinfunction "Y3_12") (pintype "output"))
    )
    (net (code "65") (name "unconnected-(IC3A-Y5-Pad10)") (class "Default")
      (node (ref "IC3") (pin "10") (pinfunction "Y5_10") (pintype "output"))
    )
    (net (code "66") (name "unconnected-(IC3A-Y6-Pad9)") (class "Default")
      (node (ref "IC3") (pin "9") (pinfunction "Y6_9") (pintype "output"))
    )
    (net (code "67") (name "unconnected-(IC3A-Y7-Pad7)") (class "Default")
      (node (ref "IC3") (pin "7") (pinfunction "Y7_7") (pintype "output"))
    )
    (net (code "68") (name "unconnected-(IC4A-Y0-Pad15)") (class "Default")
      (node (ref "IC4") (pin "15") (pinfunction "Y0_15") (pintype "output"))
    )
    (net (code "69") (name "unconnected-(IC4A-Y1-Pad14)") (class "Default")
      (node (ref "IC4") (pin "14") (pinfunction "Y1_14") (pintype "output"))
    )
    (net (code "70") (name "unconnected-(IC4A-Y2-Pad13)") (class "Default")
      (node (ref "IC4") (pin "13") (pinfunction "Y2_13") (pintype "output"))
    )
    (net (code "71") (name "unconnected-(IC4A-Y3-Pad12)") (class "Default")
      (node (ref "IC4") (pin "12") (pinfunction "Y3_12") (pintype "output"))
    )
    (net (code "72") (name "unconnected-(IC4A-Y5-Pad10)") (class "Default")
      (node (ref "IC4") (pin "10") (pinfunction "Y5_10") (pintype "output"))
    )
    (net (code "73") (name "unconnected-(IC4A-Y6-Pad9)") (class "Default")
      (node (ref "IC4") (pin "9") (pinfunction "Y6_9") (pintype "output"))
    )
    (net (code "74") (name "unconnected-(IC4A-Y7-Pad7)") (class "Default")
      (node (ref "IC4") (pin "7") (pinfunction "Y7_7") (pintype "output"))
    )
  )
)
